# microNode.net
KiCad netlist of a schematic drawn in EAGLE
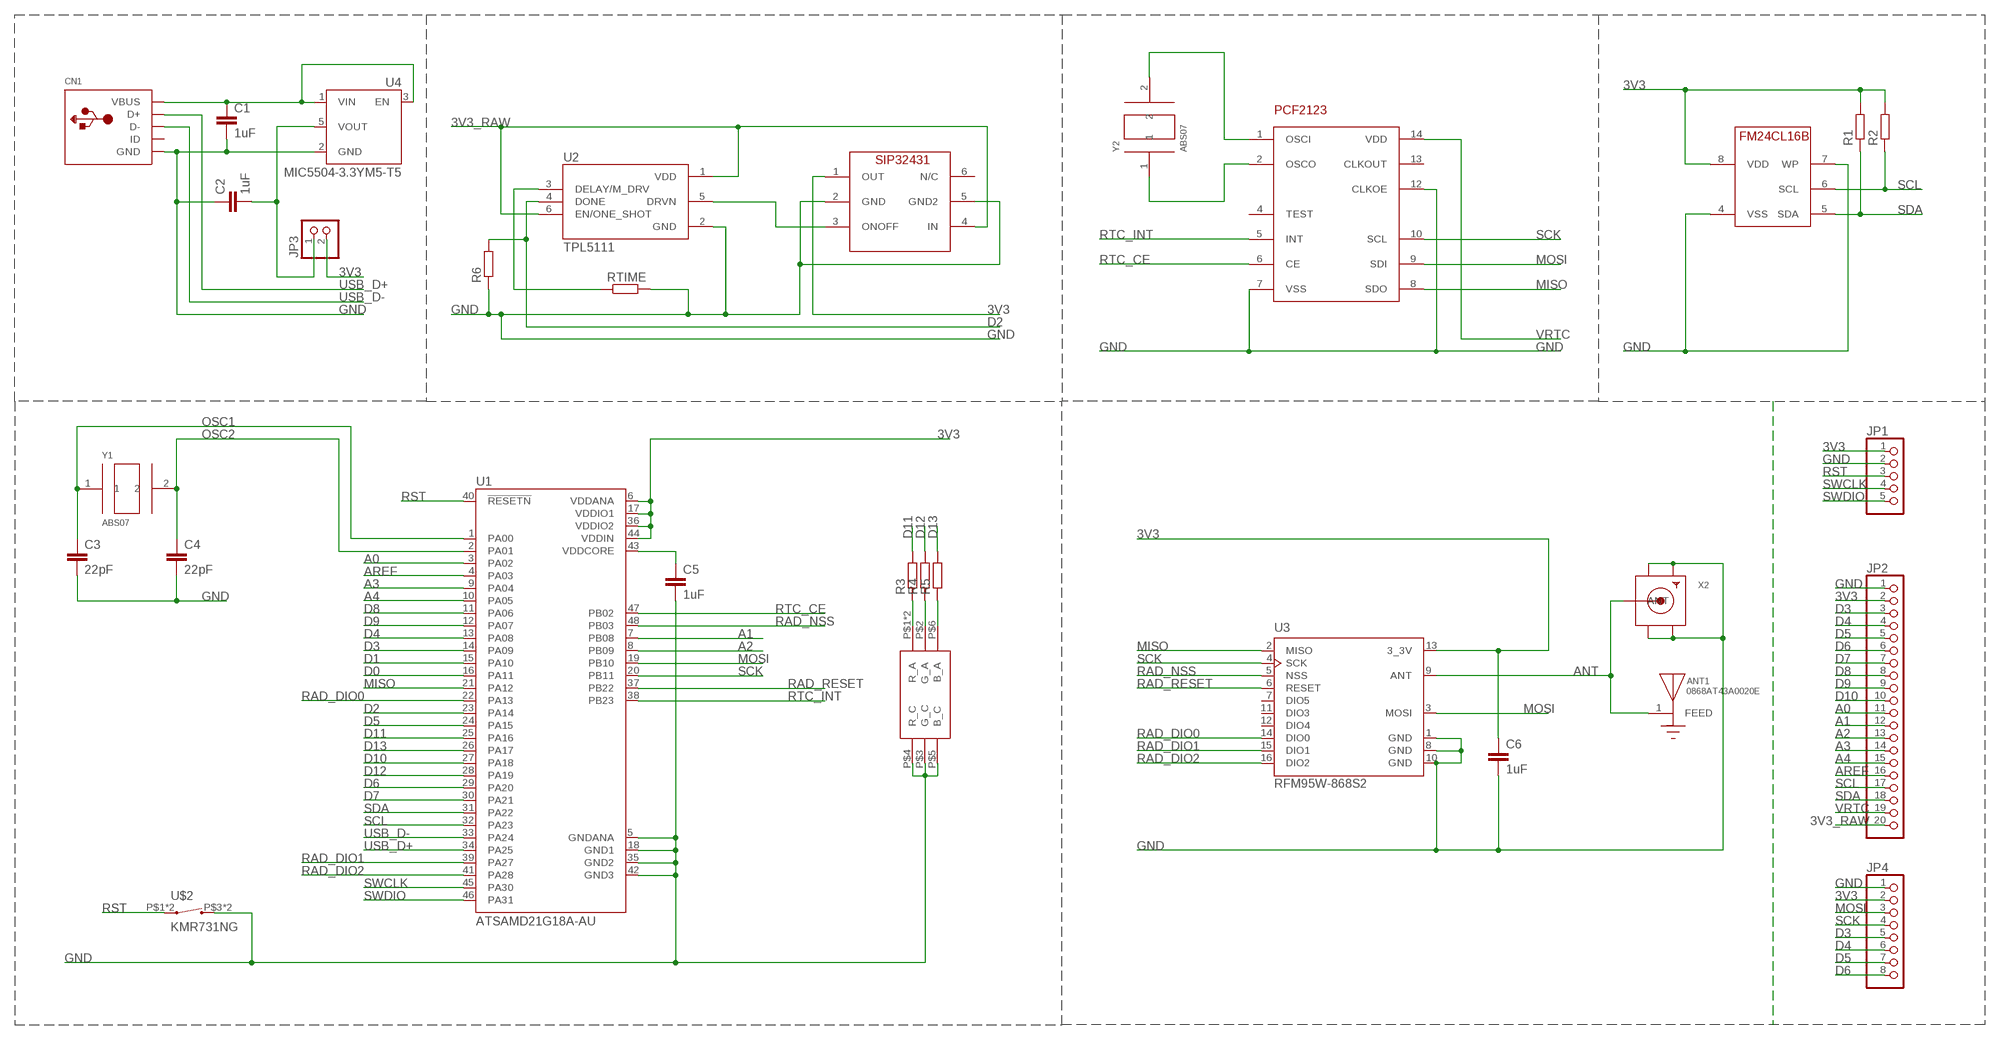
[diagram p0: schematic, sheet 1]

(export (version "E")
  (design (tool "Eeschema 10.0.6"))
  (components
    (comp (ref "ANT1")
      (value "0868AT43A0020E")
      (footprint "eagle-import:XCVR_0868AT43A0020E")
      (fields (field (name "MF") "Johanson"))
      (libsource (lib "eagle-import") (part "0868AT43A0020E"))
    )
    (comp (ref "C1")
      (value "1uF")
      (footprint "eagle-import:C1206")
      (libsource (lib "eagle-import") (part "CC1206"))
    )
    (comp (ref "C2")
      (value "1uF")
      (footprint "eagle-import:C1206")
      (libsource (lib "eagle-import") (part "CC1206"))
    )
    (comp (ref "C3")
      (value "22pF")
      (footprint "eagle-import:C0603")
      (libsource (lib "eagle-import") (part "CC0603"))
    )
    (comp (ref "C4")
      (value "22pF")
      (footprint "eagle-import:C0603")
      (libsource (lib "eagle-import") (part "CC0603"))
    )
    (comp (ref "C5")
      (value "1uF")
      (footprint "eagle-import:C1206")
      (libsource (lib "eagle-import") (part "CC1206"))
    )
    (comp (ref "C6")
      (value "1uF")
      (footprint "eagle-import:C1206")
      (libsource (lib "eagle-import") (part "CC1206"))
    )
    (comp (ref "CN1")
      (value "USBMINIB")
      (footprint "eagle-import:USB-MINIB")
      (libsource (lib "eagle-import") (part "USBMINIB"))
    )
    (comp (ref "JP1")
      (value "PINHD-1X5")
      (footprint "eagle-import:1X05")
      (libsource (lib "eagle-import") (part "PINHD-1X5"))
    )
    (comp (ref "JP2")
      (value "PINHD-1X20")
      (footprint "eagle-import:1X20")
      (libsource (lib "eagle-import") (part "PINHD-1X20"))
    )
    (comp (ref "JP3")
      (value "PINHD-1X2")
      (footprint "eagle-import:1X02")
      (libsource (lib "eagle-import") (part "PINHD-1X2"))
    )
    (comp (ref "JP4")
      (value "PINHD-1X8")
      (footprint "eagle-import:1X08")
      (libsource (lib "eagle-import") (part "PINHD-1X8"))
    )
    (comp (ref "R1")
      (value "RR0603")
      (footprint "eagle-import:R0603")
      (libsource (lib "eagle-import") (part "RR0603"))
    )
    (comp (ref "R2")
      (value "RR0603")
      (footprint "eagle-import:R0603")
      (libsource (lib "eagle-import") (part "RR0603"))
    )
    (comp (ref "R3")
      (value "RR0603")
      (footprint "eagle-import:R0603")
      (libsource (lib "eagle-import") (part "RR0603"))
    )
    (comp (ref "R4")
      (value "RR0603")
      (footprint "eagle-import:R0603")
      (libsource (lib "eagle-import") (part "RR0603"))
    )
    (comp (ref "R5")
      (value "RR0603")
      (footprint "eagle-import:R0603")
      (libsource (lib "eagle-import") (part "RR0603"))
    )
    (comp (ref "R6")
      (value "RR0603")
      (footprint "eagle-import:R0603")
      (libsource (lib "eagle-import") (part "RR0603"))
    )
    (comp (ref "RTIME")
      (value "RR1206")
      (footprint "eagle-import:R1206")
      (libsource (lib "eagle-import") (part "RR1206"))
    )
    (comp (ref "U$1")
      (value "MSL0104RGB")
      (footprint "eagle-import:MSL0104RGB")
      (libsource (lib "eagle-import") (part "MSL0104RGB"))
    )
    (comp (ref "U$2")
      (value "KMR731NG")
      (footprint "eagle-import:KMR731NG")
      (libsource (lib "eagle-import") (part "KMR731NG"))
    )
    (comp (ref "U1")
      (value "ATSAMD21G18A-AU")
      (footprint "eagle-import:QFP50P900X900X120-48N")
      (fields (field (name "MF") "Microchip"))
      (libsource (lib "eagle-import") (part "ATSAMD21G18A-AU"))
    )
    (comp (ref "U2")
      (value "TPL5111")
      (footprint "eagle-import:SOT95P280X110-6N")
      (fields (field (name "MF") "Texas Instruments") (field (name "MP") "TPL5111DDCR"))
      (libsource (lib "eagle-import") (part "TPL5111"))
    )
    (comp (ref "U3")
      (value "RFM95W-868S2")
      (footprint "eagle-import:XCVR_RFM95W-868S2")
      (fields (field (name "MF") "RF Solutions"))
      (libsource (lib "eagle-import") (part "RFM95W-868S2"))
    )
    (comp (ref "U4")
      (value "MIC5504-3.3YM5-T5")
      (footprint "eagle-import:SOT23-5P95_280X145XL45X37N")
      (fields (field (name "MF") "Microchip"))
      (libsource (lib "eagle-import") (part "MIC5504-3.3YM5-T5"))
    )
    (comp (ref "U5")
      (value "FM24CL16B")
      (footprint "eagle-import:SOIC-8")
      (libsource (lib "eagle-import") (part "FM24CL16B"))
    )
    (comp (ref "U7")
      (value "SIP32431DR3")
      (footprint "eagle-import:SC-70-6")
      (libsource (lib "eagle-import") (part "SIP32431DR3"))
    )
    (comp (ref "U8")
      (value "PCF2123")
      (footprint "eagle-import:TSSOP14")
      (libsource (lib "eagle-import") (part "PCF2123"))
    )
    (comp (ref "X2")
      (value "SMACONNECTOR")
      (footprint "eagle-import:SMA90_DIP")
      (libsource (lib "eagle-import") (part "SMACONNECTOR"))
    )
    (comp (ref "Y1")
      (value "ABS07")
      (footprint "eagle-import:XTAL320X150X90")
      (fields (field (name "MF") "Abracon") (field (name "MP") "ABS07-120-32.768KHZ-T"))
      (libsource (lib "eagle-import") (part "ABS07"))
    )
    (comp (ref "Y2")
      (value "ABS07")
      (footprint "eagle-import:XTAL320X150X90")
      (fields (field (name "MF") "Abracon") (field (name "MP") "ABS07-120-32.768KHZ-T"))
      (libsource (lib "eagle-import") (part "ABS07"))
    )
  )
  (nets
    (net (code "1") (name "/3V3") (class "Default")
      (node (ref "C6") (pin "1") (pinfunction "1_1") (pintype "passive"))
      (node (ref "JP1") (pin "1") (pinfunction "1_1") (pintype "passive"))
      (node (ref "JP2") (pin "2") (pinfunction "2_2") (pintype "passive"))
      (node (ref "JP3") (pin "2") (pinfunction "2_2") (pintype "passive"))
      (node (ref "JP4") (pin "2") (pinfunction "2_2") (pintype "passive"))
      (node (ref "R1") (pin "2") (pinfunction "2_2") (pintype "passive"))
      (node (ref "R2") (pin "2") (pinfunction "2_2") (pintype "passive"))
      (node (ref "U1") (pin "17") (pinfunction "VDDIO1_17") (pintype "power_in"))
      (node (ref "U1") (pin "36") (pinfunction "VDDIO2_36") (pintype "power_in"))
      (node (ref "U1") (pin "44") (pinfunction "VDDIN_44") (pintype "power_in"))
      (node (ref "U1") (pin "6") (pinfunction "VDDANA_6") (pintype "power_in"))
      (node (ref "U3") (pin "13") (pinfunction "3_3V_13") (pintype "power_in"))
      (node (ref "U5") (pin "8") (pinfunction "VDD_8") (pintype "bidirectional"))
      (node (ref "U7") (pin "1") (pinfunction "OUT_1") (pintype "bidirectional"))
    )
    (net (code "2") (name "/3V3_RAW") (class "Default")
      (node (ref "JP2") (pin "20") (pinfunction "20_20") (pintype "passive"))
      (node (ref "U2") (pin "1") (pinfunction "VDD_1") (pintype "power_in"))
      (node (ref "U2") (pin "6") (pinfunction "EN/ONE_SHOT_6") (pintype "input"))
      (node (ref "U7") (pin "4") (pinfunction "IN_4") (pintype "bidirectional"))
    )
    (net (code "3") (name "/A0") (class "Default")
      (node (ref "JP2") (pin "11") (pinfunction "11_11") (pintype "passive"))
      (node (ref "U1") (pin "3") (pinfunction "PA02_3") (pintype "bidirectional"))
    )
    (net (code "4") (name "/A1") (class "Default")
      (node (ref "JP2") (pin "12") (pinfunction "12_12") (pintype "passive"))
      (node (ref "U1") (pin "7") (pinfunction "PB08_7") (pintype "bidirectional"))
    )
    (net (code "5") (name "/A2") (class "Default")
      (node (ref "JP2") (pin "13") (pinfunction "13_13") (pintype "passive"))
      (node (ref "U1") (pin "8") (pinfunction "PB09_8") (pintype "bidirectional"))
    )
    (net (code "6") (name "/A3") (class "Default")
      (node (ref "JP2") (pin "14") (pinfunction "14_14") (pintype "passive"))
      (node (ref "U1") (pin "9") (pinfunction "PA04_9") (pintype "bidirectional"))
    )
    (net (code "7") (name "/A4") (class "Default")
      (node (ref "JP2") (pin "15") (pinfunction "15_15") (pintype "passive"))
      (node (ref "U1") (pin "10") (pinfunction "PA05_10") (pintype "bidirectional"))
    )
    (net (code "8") (name "/ANT") (class "Default")
      (node (ref "ANT1") (pin "1") (pinfunction "FEED_1") (pintype "input"))
      (node (ref "U3") (pin "9") (pinfunction "ANT_9") (pintype "passive"))
      (node (ref "X2") (pin "ANTENNA") (pinfunction "ANT_ANTENNA") (pintype "bidirectional"))
    )
    (net (code "9") (name "/AREF") (class "Default")
      (node (ref "JP2") (pin "16") (pinfunction "16_16") (pintype "passive"))
      (node (ref "U1") (pin "4") (pinfunction "PA03_4") (pintype "bidirectional"))
    )
    (net (code "10") (name "/D0") (class "Default")
      (node (ref "U1") (pin "16") (pinfunction "PA11_16") (pintype "bidirectional"))
    )
    (net (code "11") (name "/D1") (class "Default")
      (node (ref "U1") (pin "15") (pinfunction "PA10_15") (pintype "bidirectional"))
    )
    (net (code "12") (name "/D2") (class "Default")
      (node (ref "R6") (pin "2") (pinfunction "2_2") (pintype "passive"))
      (node (ref "U1") (pin "23") (pinfunction "PA14_23") (pintype "bidirectional"))
      (node (ref "U2") (pin "4") (pinfunction "DONE_4") (pintype "input"))
    )
    (net (code "13") (name "/D3") (class "Default")
      (node (ref "JP2") (pin "3") (pinfunction "3_3") (pintype "passive"))
      (node (ref "JP4") (pin "5") (pinfunction "5_5") (pintype "passive"))
      (node (ref "U1") (pin "14") (pinfunction "PA09_14") (pintype "bidirectional"))
    )
    (net (code "14") (name "/D4") (class "Default")
      (node (ref "JP2") (pin "4") (pinfunction "4_4") (pintype "passive"))
      (node (ref "JP4") (pin "6") (pinfunction "6_6") (pintype "passive"))
      (node (ref "U1") (pin "13") (pinfunction "PA08_13") (pintype "bidirectional"))
    )
    (net (code "15") (name "/D5") (class "Default")
      (node (ref "JP2") (pin "5") (pinfunction "5_5") (pintype "passive"))
      (node (ref "JP4") (pin "7") (pinfunction "7_7") (pintype "passive"))
      (node (ref "U1") (pin "24") (pinfunction "PA15_24") (pintype "bidirectional"))
    )
    (net (code "16") (name "/D6") (class "Default")
      (node (ref "JP2") (pin "6") (pinfunction "6_6") (pintype "passive"))
      (node (ref "JP4") (pin "8") (pinfunction "8_8") (pintype "passive"))
      (node (ref "U1") (pin "29") (pinfunction "PA20_29") (pintype "bidirectional"))
    )
    (net (code "17") (name "/D7") (class "Default")
      (node (ref "JP2") (pin "7") (pinfunction "7_7") (pintype "passive"))
      (node (ref "U1") (pin "30") (pinfunction "PA21_30") (pintype "bidirectional"))
    )
    (net (code "18") (name "/D8") (class "Default")
      (node (ref "JP2") (pin "8") (pinfunction "8_8") (pintype "passive"))
      (node (ref "U1") (pin "11") (pinfunction "PA06_11") (pintype "bidirectional"))
    )
    (net (code "19") (name "/D9") (class "Default")
      (node (ref "JP2") (pin "9") (pinfunction "9_9") (pintype "passive"))
      (node (ref "U1") (pin "12") (pinfunction "PA07_12") (pintype "bidirectional"))
    )
    (net (code "20") (name "/D10") (class "Default")
      (node (ref "JP2") (pin "10") (pinfunction "10_10") (pintype "passive"))
      (node (ref "U1") (pin "27") (pinfunction "PA18_27") (pintype "bidirectional"))
    )
    (net (code "21") (name "/D11") (class "Default")
      (node (ref "R3") (pin "2") (pinfunction "2_2") (pintype "passive"))
      (node (ref "U1") (pin "25") (pinfunction "PA16_25") (pintype "bidirectional"))
    )
    (net (code "22") (name "/D12") (class "Default")
      (node (ref "R4") (pin "2") (pinfunction "2_2") (pintype "passive"))
      (node (ref "U1") (pin "28") (pinfunction "PA19_28") (pintype "bidirectional"))
    )
    (net (code "23") (name "/D13") (class "Default")
      (node (ref "R5") (pin "2") (pinfunction "2_2") (pintype "passive"))
      (node (ref "U1") (pin "26") (pinfunction "PA17_26") (pintype "bidirectional"))
    )
    (net (code "24") (name "/GND") (class "Default")
      (node (ref "C1") (pin "2") (pinfunction "2_2") (pintype "passive"))
      (node (ref "C2") (pin "1") (pinfunction "1_1") (pintype "passive"))
      (node (ref "C3") (pin "2") (pinfunction "2_2") (pintype "passive"))
      (node (ref "C4") (pin "2") (pinfunction "2_2") (pintype "passive"))
      (node (ref "C5") (pin "2") (pinfunction "2_2") (pintype "passive"))
      (node (ref "C6") (pin "2") (pinfunction "2_2") (pintype "passive"))
      (node (ref "CN1") (pin "GND") (pinfunction "GND_GND") (pintype "power_in"))
      (node (ref "JP1") (pin "2") (pinfunction "2_2") (pintype "passive"))
      (node (ref "JP2") (pin "1") (pinfunction "1_1") (pintype "passive"))
      (node (ref "JP4") (pin "1") (pinfunction "1_1") (pintype "passive"))
      (node (ref "R6") (pin "1") (pinfunction "1_1") (pintype "passive"))
      (node (ref "RTIME") (pin "2") (pinfunction "2_2") (pintype "passive"))
      (node (ref "U$1") (pin "P$3") (pinfunction "G_C_P$3") (pintype "bidirectional"))
      (node (ref "U$1") (pin "P$4") (pinfunction "R_C_P$4") (pintype "bidirectional"))
      (node (ref "U$1") (pin "P$5") (pinfunction "B_C_P$5") (pintype "bidirectional"))
      (node (ref "U$2") (pin "P$3") (pinfunction "2_P$3") (pintype "passive"))
      (node (ref "U$2") (pin "P$4") (pinfunction "2_P$4") (pintype "passive"))
      (node (ref "U1") (pin "18") (pinfunction "GND1_18") (pintype "power_in"))
      (node (ref "U1") (pin "35") (pinfunction "GND2_35") (pintype "power_in"))
      (node (ref "U1") (pin "42") (pinfunction "GND3_42") (pintype "power_in"))
      (node (ref "U1") (pin "5") (pinfunction "GNDANA_5") (pintype "power_in"))
      (node (ref "U2") (pin "2") (pinfunction "GND_2") (pintype "power_in"))
      (node (ref "U3") (pin "1") (pinfunction "GND_1") (pintype "power_in"))
      (node (ref "U3") (pin "10") (pinfunction "GND_10") (pintype "power_in"))
      (node (ref "U3") (pin "8") (pinfunction "GND_8") (pintype "power_in"))
      (node (ref "U4") (pin "2") (pinfunction "GND_2") (pintype "power_in"))
      (node (ref "U5") (pin "4") (pinfunction "VSS_4") (pintype "bidirectional"))
      (node (ref "U5") (pin "7") (pinfunction "WP_7") (pintype "bidirectional"))
      (node (ref "U7") (pin "2") (pinfunction "GND_2") (pintype "bidirectional"))
      (node (ref "U7") (pin "5") (pinfunction "GND2_5") (pintype "bidirectional"))
      (node (ref "U8") (pin "12") (pinfunction "CLKOE_12") (pintype "bidirectional"))
      (node (ref "U8") (pin "7") (pinfunction "VSS_7") (pintype "bidirectional"))
      (node (ref "X2") (pin "GND1") (pinfunction "GND1_GND1") (pintype "power_in"))
      (node (ref "X2") (pin "GND2") (pinfunction "GND2_GND2") (pintype "power_in"))
      (node (ref "X2") (pin "GND3") (pinfunction "GND3_GND3") (pintype "power_in"))
      (node (ref "X2") (pin "GND4") (pinfunction "GND4_GND4") (pintype "power_in"))
    )
    (net (code "25") (name "/MISO") (class "Default")
      (node (ref "U1") (pin "21") (pinfunction "PA12_21") (pintype "bidirectional"))
      (node (ref "U3") (pin "2") (pinfunction "MISO_2") (pintype "input"))
      (node (ref "U8") (pin "8") (pinfunction "SDO_8") (pintype "bidirectional"))
    )
    (net (code "26") (name "/MOSI") (class "Default")
      (node (ref "JP4") (pin "3") (pinfunction "3_3") (pintype "passive"))
      (node (ref "U1") (pin "19") (pinfunction "PB10_19") (pintype "bidirectional"))
      (node (ref "U3") (pin "3") (pinfunction "MOSI_3") (pintype "output"))
      (node (ref "U8") (pin "9") (pinfunction "SDI_9") (pintype "bidirectional"))
    )
    (net (code "27") (name "/OSC1") (class "Default")
      (node (ref "C3") (pin "1") (pinfunction "1_1") (pintype "passive"))
      (node (ref "U1") (pin "1") (pinfunction "PA00_1") (pintype "bidirectional"))
      (node (ref "Y1") (pin "1") (pinfunction "1_1") (pintype "passive"))
    )
    (net (code "28") (name "/OSC2") (class "Default")
      (node (ref "C4") (pin "1") (pinfunction "1_1") (pintype "passive"))
      (node (ref "U1") (pin "2") (pinfunction "PA01_2") (pintype "bidirectional"))
      (node (ref "Y1") (pin "2") (pinfunction "2_2") (pintype "passive"))
    )
    (net (code "29") (name "/RAD_DIO0") (class "Default")
      (node (ref "U1") (pin "22") (pinfunction "PA13_22") (pintype "bidirectional"))
      (node (ref "U3") (pin "14") (pinfunction "DIO0_14") (pintype "bidirectional"))
    )
    (net (code "30") (name "/RAD_DIO1") (class "Default")
      (node (ref "U1") (pin "39") (pinfunction "PA27_39") (pintype "bidirectional"))
      (node (ref "U3") (pin "15") (pinfunction "DIO1_15") (pintype "bidirectional"))
    )
    (net (code "31") (name "/RAD_DIO2") (class "Default")
      (node (ref "U1") (pin "41") (pinfunction "PA28_41") (pintype "bidirectional"))
      (node (ref "U3") (pin "16") (pinfunction "DIO2_16") (pintype "bidirectional"))
    )
    (net (code "32") (name "/RAD_NSS") (class "Default")
      (node (ref "U1") (pin "48") (pinfunction "PB03_48") (pintype "bidirectional"))
      (node (ref "U3") (pin "5") (pinfunction "NSS_5") (pintype "input"))
    )
    (net (code "33") (name "/RAD_RESET") (class "Default")
      (node (ref "U1") (pin "37") (pinfunction "PB22_37") (pintype "bidirectional"))
      (node (ref "U3") (pin "6") (pinfunction "RESET_6") (pintype "bidirectional"))
    )
    (net (code "34") (name "/RST") (class "Default")
      (node (ref "JP1") (pin "3") (pinfunction "3_3") (pintype "passive"))
      (node (ref "U$2") (pin "P$1") (pinfunction "1_P$1") (pintype "passive"))
      (node (ref "U$2") (pin "P$2") (pinfunction "1_P$2") (pintype "passive"))
      (node (ref "U1") (pin "40") (pinfunction "~{RESETN}_40") (pintype "input"))
    )
    (net (code "35") (name "/RTC_CE") (class "Default")
      (node (ref "U1") (pin "47") (pinfunction "PB02_47") (pintype "bidirectional"))
      (node (ref "U8") (pin "6") (pinfunction "CE_6") (pintype "bidirectional"))
    )
    (net (code "36") (name "/RTC_INT") (class "Default")
      (node (ref "U1") (pin "38") (pinfunction "PB23_38") (pintype "bidirectional"))
      (node (ref "U8") (pin "5") (pinfunction "INT_5") (pintype "bidirectional"))
    )
    (net (code "37") (name "/SCK") (class "Default")
      (node (ref "JP4") (pin "4") (pinfunction "4_4") (pintype "passive"))
      (node (ref "U1") (pin "20") (pinfunction "PB11_20") (pintype "bidirectional"))
      (node (ref "U3") (pin "4") (pinfunction "SCK_4") (pintype "input"))
      (node (ref "U8") (pin "10") (pinfunction "SCL_10") (pintype "bidirectional"))
    )
    (net (code "38") (name "/SCL") (class "Default")
      (node (ref "JP2") (pin "17") (pinfunction "17_17") (pintype "passive"))
      (node (ref "R2") (pin "1") (pinfunction "1_1") (pintype "passive"))
      (node (ref "U1") (pin "32") (pinfunction "PA23_32") (pintype "bidirectional"))
      (node (ref "U5") (pin "6") (pinfunction "SCL_6") (pintype "bidirectional"))
    )
    (net (code "39") (name "/SDA") (class "Default")
      (node (ref "JP2") (pin "18") (pinfunction "18_18") (pintype "passive"))
      (node (ref "R1") (pin "1") (pinfunction "1_1") (pintype "passive"))
      (node (ref "U1") (pin "31") (pinfunction "PA22_31") (pintype "bidirectional"))
      (node (ref "U5") (pin "5") (pinfunction "SDA_5") (pintype "bidirectional"))
    )
    (net (code "40") (name "/SWCLK") (class "Default")
      (node (ref "JP1") (pin "4") (pinfunction "4_4") (pintype "passive"))
      (node (ref "U1") (pin "45") (pinfunction "PA30_45") (pintype "bidirectional"))
    )
    (net (code "41") (name "/SWDIO") (class "Default")
      (node (ref "JP1") (pin "5") (pinfunction "5_5") (pintype "passive"))
      (node (ref "U1") (pin "46") (pinfunction "PA31_46") (pintype "bidirectional"))
    )
    (net (code "42") (name "/USB_D+") (class "Default")
      (node (ref "CN1") (pin "D+") (pinfunction "D+_D+") (pintype "bidirectional"))
      (node (ref "U1") (pin "34") (pinfunction "PA25_34") (pintype "bidirectional"))
    )
    (net (code "43") (name "/USB_D-") (class "Default")
      (node (ref "CN1") (pin "D-") (pinfunction "D-_D-") (pintype "bidirectional"))
      (node (ref "U1") (pin "33") (pinfunction "PA24_33") (pintype "bidirectional"))
    )
    (net (code "44") (name "/VRTC") (class "Default")
      (node (ref "JP2") (pin "19") (pinfunction "19_19") (pintype "passive"))
      (node (ref "U8") (pin "14") (pinfunction "VDD_14") (pintype "bidirectional"))
    )
    (net (code "45") (name "Net-(R3-Pad1)") (class "Default")
      (node (ref "R3") (pin "1") (pinfunction "1_1") (pintype "passive"))
      (node (ref "U$1") (pin "P$1") (pinfunction "R_A_P$1") (pintype "bidirectional"))
      (node (ref "U$1") (pin "P$7") (pinfunction "R_A_P$7") (pintype "bidirectional"))
    )
    (net (code "46") (name "Net-(U$1-B_A)") (class "Default")
      (node (ref "R5") (pin "1") (pinfunction "1_1") (pintype "passive"))
      (node (ref "U$1") (pin "P$6") (pinfunction "B_A_P$6") (pintype "bidirectional"))
    )
    (net (code "47") (name "Net-(U$1-G_A)") (class "Default")
      (node (ref "R4") (pin "1") (pinfunction "1_1") (pintype "passive"))
      (node (ref "U$1") (pin "P$2") (pinfunction "G_A_P$2") (pintype "bidirectional"))
    )
    (net (code "48") (name "Net-(U1-VDDCORE)") (class "Default")
      (node (ref "C5") (pin "1") (pinfunction "1_1") (pintype "passive"))
      (node (ref "U1") (pin "43") (pinfunction "VDDCORE_43") (pintype "power_in"))
    )
    (net (code "49") (name "Net-(U2-DELAY{slash}M_DRV)") (class "Default")
      (node (ref "RTIME") (pin "1") (pinfunction "1_1") (pintype "passive"))
      (node (ref "U2") (pin "3") (pinfunction "DELAY/M_DRV_3") (pintype "input"))
    )
    (net (code "50") (name "Net-(U2-DRVN)") (class "Default")
      (node (ref "U2") (pin "5") (pinfunction "DRVN_5") (pintype "output"))
      (node (ref "U7") (pin "3") (pinfunction "ONOFF_3") (pintype "bidirectional"))
    )
    (net (code "51") (name "Net-(U4-EN)") (class "Default")
      (node (ref "C1") (pin "1") (pinfunction "1_1") (pintype "passive"))
      (node (ref "CN1") (pin "VBUS") (pinfunction "VBUS_VBUS") (pintype "power_in"))
      (node (ref "U4") (pin "1") (pinfunction "VIN_1") (pintype "power_in"))
      (node (ref "U4") (pin "3") (pinfunction "EN_3") (pintype "input"))
    )
    (net (code "52") (name "Net-(U4-VOUT)") (class "Default")
      (node (ref "C2") (pin "2") (pinfunction "2_2") (pintype "passive"))
      (node (ref "JP3") (pin "1") (pinfunction "1_1") (pintype "passive"))
      (node (ref "U4") (pin "5") (pinfunction "VOUT_5") (pintype "output"))
    )
    (net (code "53") (name "Net-(U8-OSCI)") (class "Default")
      (node (ref "U8") (pin "1") (pinfunction "OSCI_1") (pintype "bidirectional"))
      (node (ref "Y2") (pin "2") (pinfunction "2_2") (pintype "passive"))
    )
    (net (code "54") (name "Net-(U8-OSCO)") (class "Default")
      (node (ref "U8") (pin "2") (pinfunction "OSCO_2") (pintype "bidirectional"))
      (node (ref "Y2") (pin "1") (pinfunction "1_1") (pintype "passive"))
    )
    (net (code "55") (name "unconnected-(CN1-PadID)") (class "Default")
      (node (ref "CN1") (pin "ID") (pinfunction "ID_ID") (pintype "bidirectional"))
    )
    (net (code "56") (name "unconnected-(U3-DIO3-Pad11)") (class "Default")
      (node (ref "U3") (pin "11") (pinfunction "DIO3_11") (pintype "bidirectional"))
    )
    (net (code "57") (name "unconnected-(U3-DIO4-Pad12)") (class "Default")
      (node (ref "U3") (pin "12") (pinfunction "DIO4_12") (pintype "bidirectional"))
    )
    (net (code "58") (name "unconnected-(U3-DIO5-Pad7)") (class "Default")
      (node (ref "U3") (pin "7") (pinfunction "DIO5_7") (pintype "bidirectional"))
    )
    (net (code "59") (name "unconnected-(U7-N{slash}C-Pad6)") (class "Default")
      (node (ref "U7") (pin "6") (pinfunction "N/C_6") (pintype "bidirectional"))
    )
    (net (code "60") (name "unconnected-(U8-CLKOUT-Pad13)") (class "Default")
      (node (ref "U8") (pin "13") (pinfunction "CLKOUT_13") (pintype "bidirectional"))
    )
    (net (code "61") (name "unconnected-(U8-TEST-Pad4)") (class "Default")
      (node (ref "U8") (pin "4") (pinfunction "TEST_4") (pintype "bidirectional"))
    )
  )
)
